# gps-carrier.net
KiCad netlist of a schematic drawn in EAGLE
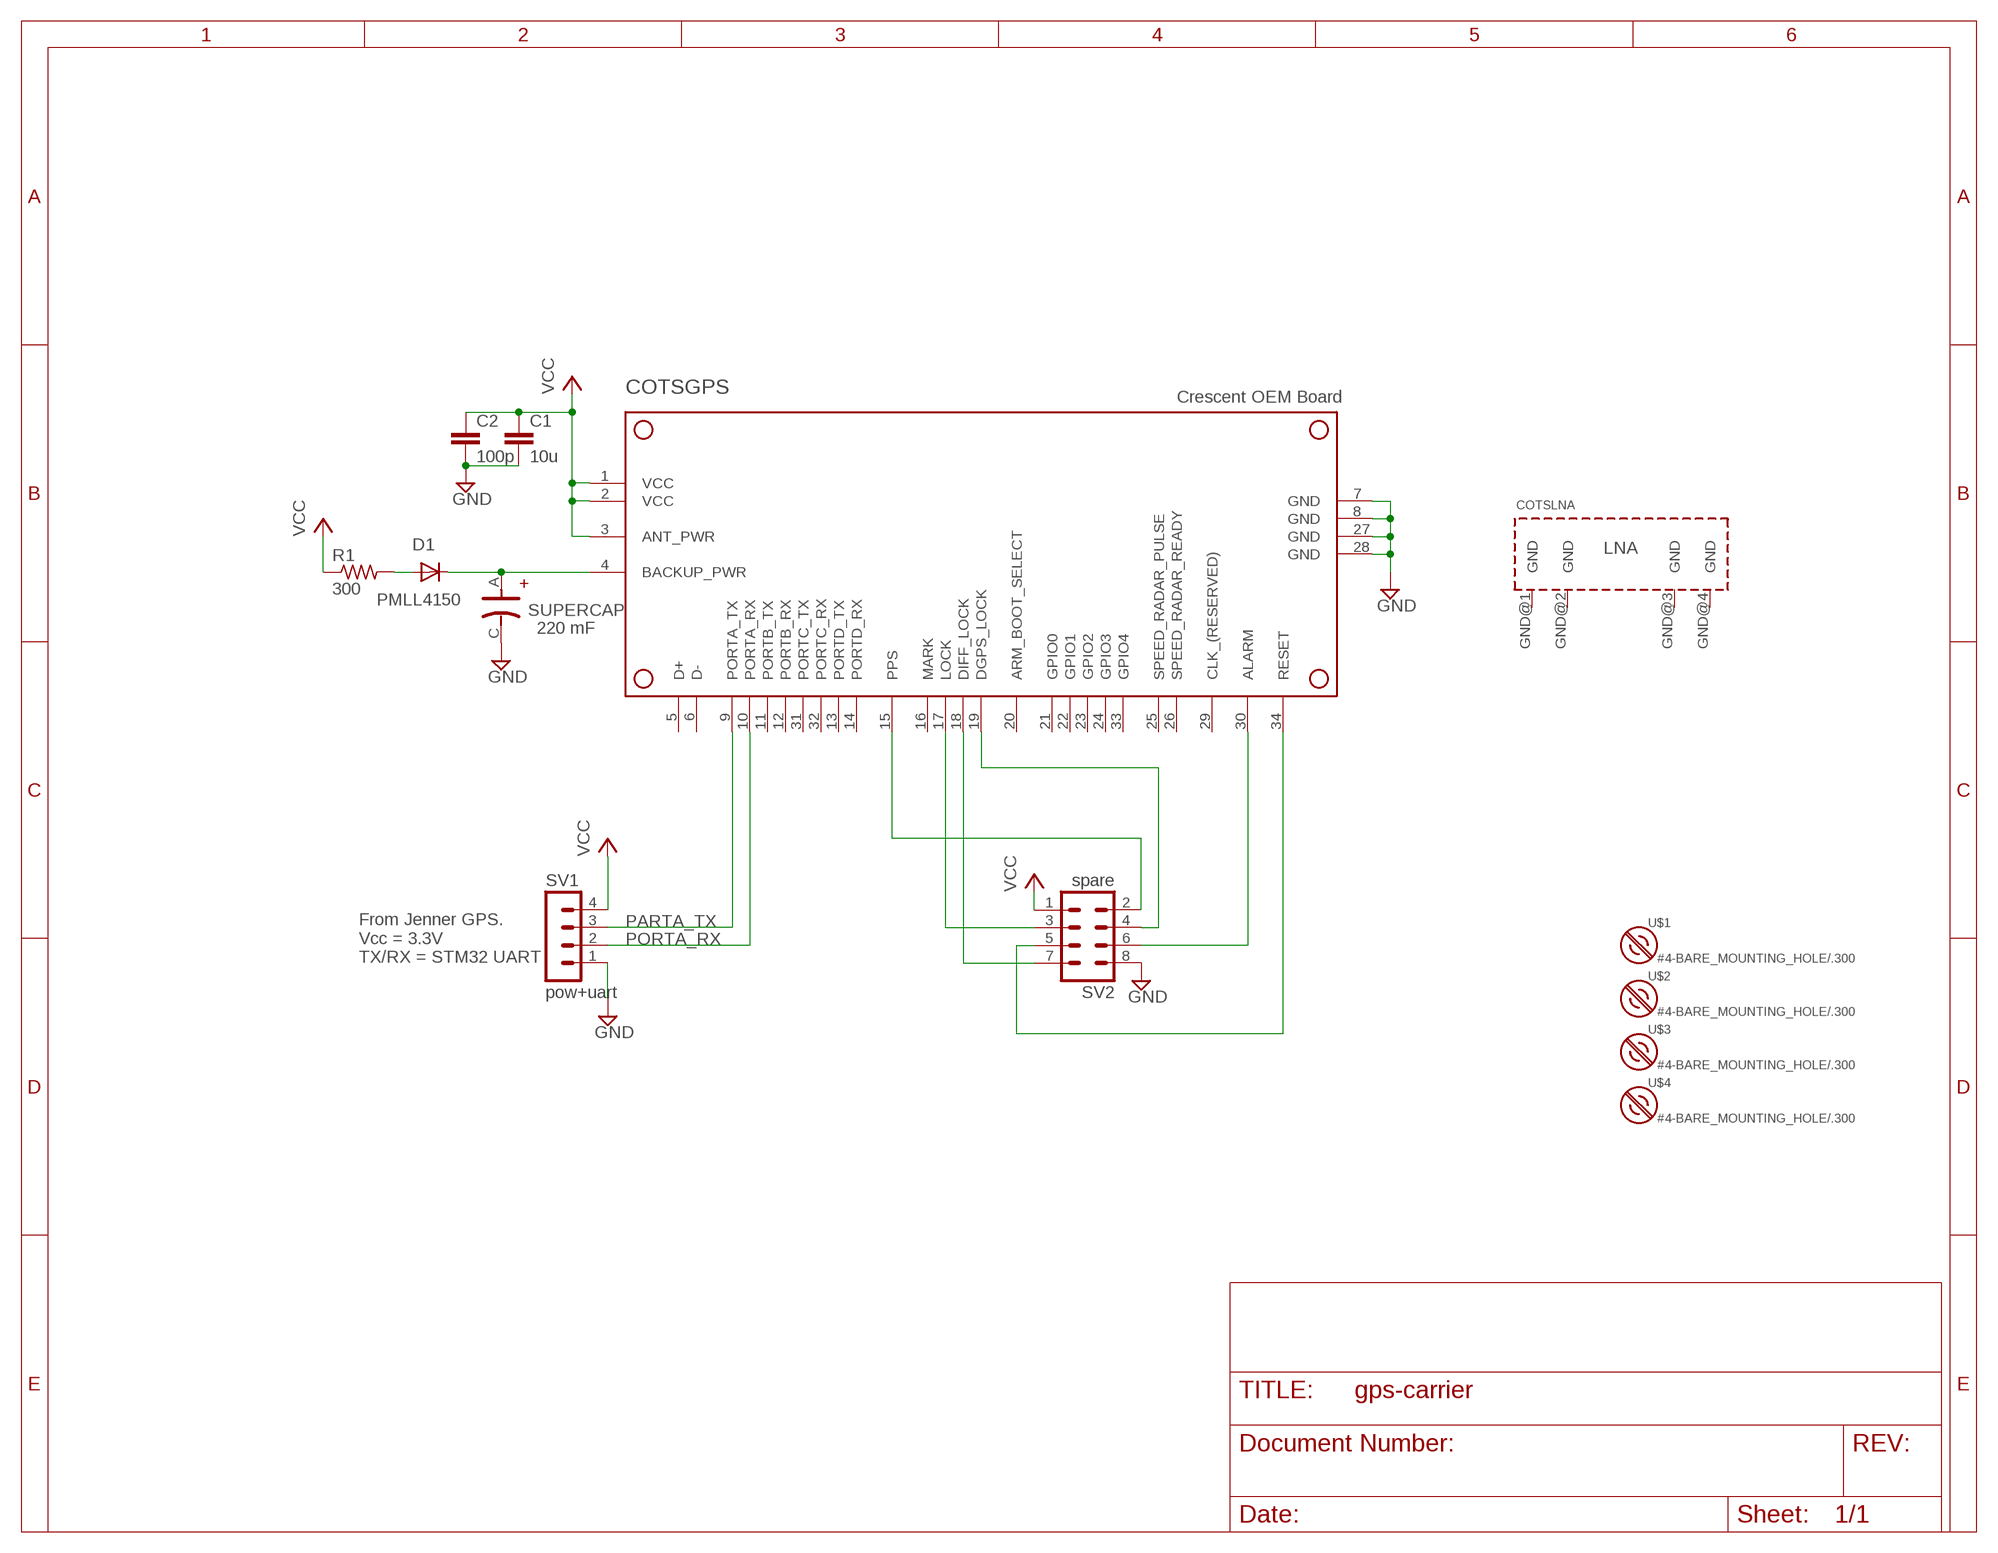
[diagram p0: schematic, sheet 1]

(export (version "E")
  (design (tool "Eeschema 10.0.6"))
  (components
    (comp (ref "C1")
      (value "10u")
      (footprint "eagle-import:C0805")
      (libsource (lib "eagle-import") (part "C-EUC0805"))
    )
    (comp (ref "C2")
      (value "100p")
      (footprint "eagle-import:C0603")
      (libsource (lib "eagle-import") (part "C-EUC0603"))
    )
    (comp (ref "COTSGPS")
      (value "HEMISPHERE_GPS_MOUNT")
      (footprint "eagle-import:GPS_CRECENT_OUTLINE")
      (libsource (lib "eagle-import") (part "HEMISPHERE_GPS_MOUNT"))
    )
    (comp (ref "COTSLNA")
      (value "GPS_LNA")
      (footprint "eagle-import:GPS_LNA")
      (libsource (lib "eagle-import") (part "GPS_LNA"))
    )
    (comp (ref "D1")
      (value "PMLL4150")
      (footprint "eagle-import:SOD80C")
      (libsource (lib "eagle-import") (part "PMLL4150"))
    )
    (comp (ref "R1")
      (value "300")
      (footprint "eagle-import:R0603")
      (libsource (lib "eagle-import") (part "R-US_R0603"))
    )
    (comp (ref "SUPERCAP")
      (value "220 mF")
      (footprint "eagle-import:DSK-HL")
      (libsource (lib "eagle-import") (part "DSK-3R3H224U-HL"))
    )
    (comp (ref "SV1")
      (value "pow+uart")
      (footprint "eagle-import:MA04-1")
      (libsource (lib "eagle-import") (part "MA04-1"))
    )
    (comp (ref "SV2")
      (value "spare")
      (footprint "eagle-import:MA04-2")
      (libsource (lib "eagle-import") (part "MA04-2"))
    )
    (comp (ref "U$1")
      (value "#4-BARE_MOUNTING_HOLE/.300")
      (footprint "eagle-import:#4_.300-BARE+STD_NUT_OR_STAR_WASHER")
      (libsource (lib "eagle-import") (part "#4-BARE_MOUNTING_HOLE/.300"))
    )
    (comp (ref "U$2")
      (value "#4-BARE_MOUNTING_HOLE/.300")
      (footprint "eagle-import:#4_.300-BARE+STD_NUT_OR_STAR_WASHER")
      (libsource (lib "eagle-import") (part "#4-BARE_MOUNTING_HOLE/.300"))
    )
    (comp (ref "U$3")
      (value "#4-BARE_MOUNTING_HOLE/.300")
      (footprint "eagle-import:#4_.300-BARE+STD_NUT_OR_STAR_WASHER")
      (libsource (lib "eagle-import") (part "#4-BARE_MOUNTING_HOLE/.300"))
    )
    (comp (ref "U$4")
      (value "#4-BARE_MOUNTING_HOLE/.300")
      (footprint "eagle-import:#4_.300-BARE+STD_NUT_OR_STAR_WASHER")
      (libsource (lib "eagle-import") (part "#4-BARE_MOUNTING_HOLE/.300"))
    )
  )
  (nets
    (net (code "1") (name "/PARTA_TX") (class "Default")
      (node (ref "COTSGPS") (pin "9") (pinfunction "PORTA_TX_9") (pintype "bidirectional"))
      (node (ref "SV1") (pin "3") (pinfunction "3_3") (pintype "passive"))
    )
    (net (code "2") (name "/PORTA_RX") (class "Default")
      (node (ref "COTSGPS") (pin "10") (pinfunction "PORTA_RX_10") (pintype "bidirectional"))
      (node (ref "SV1") (pin "2") (pinfunction "2_2") (pintype "passive"))
    )
    (net (code "3") (name "GND") (class "Default")
      (node (ref "C1") (pin "2") (pinfunction "2_2") (pintype "passive"))
      (node (ref "C2") (pin "2") (pinfunction "2_2") (pintype "passive"))
      (node (ref "COTSGPS") (pin "27") (pinfunction "GND_27") (pintype "bidirectional"))
      (node (ref "COTSGPS") (pin "28") (pinfunction "GND_28") (pintype "bidirectional"))
      (node (ref "COTSGPS") (pin "7") (pinfunction "GND_7") (pintype "bidirectional"))
      (node (ref "COTSGPS") (pin "8") (pinfunction "GND_8") (pintype "bidirectional"))
      (node (ref "SUPERCAP") (pin "C") (pinfunction "C_C") (pintype "bidirectional"))
      (node (ref "SV1") (pin "1") (pinfunction "1_1") (pintype "passive"))
      (node (ref "SV2") (pin "8") (pinfunction "8_8") (pintype "passive"))
    )
    (net (code "4") (name "Net-(COTSGPS-ALARM)") (class "Default")
      (node (ref "COTSGPS") (pin "30") (pinfunction "ALARM_30") (pintype "bidirectional"))
      (node (ref "SV2") (pin "6") (pinfunction "6_6") (pintype "passive"))
    )
    (net (code "5") (name "Net-(COTSGPS-BACKUP_PWR)") (class "Default")
      (node (ref "COTSGPS") (pin "4") (pinfunction "BACKUP_PWR_4") (pintype "bidirectional"))
      (node (ref "D1") (pin "C") (pinfunction "C_C") (pintype "passive"))
      (node (ref "SUPERCAP") (pin "A") (pinfunction "A_A") (pintype "bidirectional"))
    )
    (net (code "6") (name "Net-(COTSGPS-DGPS_LOCK)") (class "Default")
      (node (ref "COTSGPS") (pin "19") (pinfunction "DGPS_LOCK_19") (pintype "bidirectional"))
      (node (ref "SV2") (pin "4") (pinfunction "4_4") (pintype "passive"))
    )
    (net (code "7") (name "Net-(COTSGPS-DIFF_LOCK)") (class "Default")
      (node (ref "COTSGPS") (pin "18") (pinfunction "DIFF_LOCK_18") (pintype "bidirectional"))
      (node (ref "SV2") (pin "7") (pinfunction "7_7") (pintype "passive"))
    )
    (net (code "8") (name "Net-(COTSGPS-LOCK)") (class "Default")
      (node (ref "COTSGPS") (pin "17") (pinfunction "LOCK_17") (pintype "bidirectional"))
      (node (ref "SV2") (pin "3") (pinfunction "3_3") (pintype "passive"))
    )
    (net (code "9") (name "Net-(COTSGPS-PPS)") (class "Default")
      (node (ref "COTSGPS") (pin "15") (pinfunction "PPS_15") (pintype "bidirectional"))
      (node (ref "SV2") (pin "2") (pinfunction "2_2") (pintype "passive"))
    )
    (net (code "10") (name "Net-(COTSGPS-RESET)") (class "Default")
      (node (ref "COTSGPS") (pin "34") (pinfunction "RESET_34") (pintype "bidirectional"))
      (node (ref "SV2") (pin "5") (pinfunction "5_5") (pintype "passive"))
    )
    (net (code "11") (name "Net-(D1-PadA)") (class "Default")
      (node (ref "D1") (pin "A") (pinfunction "A_A") (pintype "passive"))
      (node (ref "R1") (pin "2") (pinfunction "2_2") (pintype "passive"))
    )
    (net (code "12") (name "VCC") (class "Default")
      (node (ref "C1") (pin "1") (pinfunction "1_1") (pintype "passive"))
      (node (ref "C2") (pin "1") (pinfunction "1_1") (pintype "passive"))
      (node (ref "COTSGPS") (pin "1") (pinfunction "VCC_1") (pintype "bidirectional"))
      (node (ref "COTSGPS") (pin "2") (pinfunction "VCC_2") (pintype "bidirectional"))
      (node (ref "COTSGPS") (pin "3") (pinfunction "ANT_PWR_3") (pintype "bidirectional"))
      (node (ref "R1") (pin "1") (pinfunction "1_1") (pintype "passive"))
      (node (ref "SV1") (pin "4") (pinfunction "4_4") (pintype "passive"))
      (node (ref "SV2") (pin "1") (pinfunction "1_1") (pintype "passive"))
    )
    (net (code "13") (name "unconnected-(COTSGPS-ARM_BOOT_SELECT-Pad20)") (class "Default")
      (node (ref "COTSGPS") (pin "20") (pinfunction "ARM_BOOT_SELECT_20") (pintype "bidirectional"))
    )
    (net (code "14") (name "unconnected-(COTSGPS-CLK_(RESERVED)-Pad29)") (class "Default")
      (node (ref "COTSGPS") (pin "29") (pinfunction "CLK_(RESERVED)_29") (pintype "bidirectional"))
    )
    (net (code "15") (name "unconnected-(COTSGPS-D+-Pad5)") (class "Default")
      (node (ref "COTSGPS") (pin "5") (pinfunction "D+_5") (pintype "bidirectional"))
    )
    (net (code "16") (name "unconnected-(COTSGPS-D--Pad6)") (class "Default")
      (node (ref "COTSGPS") (pin "6") (pinfunction "D-_6") (pintype "bidirectional"))
    )
    (net (code "17") (name "unconnected-(COTSGPS-GPIO0-Pad21)") (class "Default")
      (node (ref "COTSGPS") (pin "21") (pinfunction "GPIO0_21") (pintype "bidirectional"))
    )
    (net (code "18") (name "unconnected-(COTSGPS-GPIO1-Pad22)") (class "Default")
      (node (ref "COTSGPS") (pin "22") (pinfunction "GPIO1_22") (pintype "bidirectional"))
    )
    (net (code "19") (name "unconnected-(COTSGPS-GPIO2-Pad23)") (class "Default")
      (node (ref "COTSGPS") (pin "23") (pinfunction "GPIO2_23") (pintype "bidirectional"))
    )
    (net (code "20") (name "unconnected-(COTSGPS-GPIO3-Pad24)") (class "Default")
      (node (ref "COTSGPS") (pin "24") (pinfunction "GPIO3_24") (pintype "bidirectional"))
    )
    (net (code "21") (name "unconnected-(COTSGPS-GPIO4-Pad33)") (class "Default")
      (node (ref "COTSGPS") (pin "33") (pinfunction "GPIO4_33") (pintype "bidirectional"))
    )
    (net (code "22") (name "unconnected-(COTSGPS-MARK-Pad16)") (class "Default")
      (node (ref "COTSGPS") (pin "16") (pinfunction "MARK_16") (pintype "bidirectional"))
    )
    (net (code "23") (name "unconnected-(COTSGPS-PORTB_RX-Pad12)") (class "Default")
      (node (ref "COTSGPS") (pin "12") (pinfunction "PORTB_RX_12") (pintype "bidirectional"))
    )
    (net (code "24") (name "unconnected-(COTSGPS-PORTB_TX-Pad11)") (class "Default")
      (node (ref "COTSGPS") (pin "11") (pinfunction "PORTB_TX_11") (pintype "bidirectional"))
    )
    (net (code "25") (name "unconnected-(COTSGPS-PORTC_RX-Pad32)") (class "Default")
      (node (ref "COTSGPS") (pin "32") (pinfunction "PORTC_RX_32") (pintype "bidirectional"))
    )
    (net (code "26") (name "unconnected-(COTSGPS-PORTC_TX-Pad31)") (class "Default")
      (node (ref "COTSGPS") (pin "31") (pinfunction "PORTC_TX_31") (pintype "bidirectional"))
    )
    (net (code "27") (name "unconnected-(COTSGPS-PORTD_RX-Pad14)") (class "Default")
      (node (ref "COTSGPS") (pin "14") (pinfunction "PORTD_RX_14") (pintype "bidirectional"))
    )
    (net (code "28") (name "unconnected-(COTSGPS-PORTD_TX-Pad13)") (class "Default")
      (node (ref "COTSGPS") (pin "13") (pinfunction "PORTD_TX_13") (pintype "bidirectional"))
    )
    (net (code "29") (name "unconnected-(COTSGPS-SPEED_RADAR_PULSE-Pad25)") (class "Default")
      (node (ref "COTSGPS") (pin "25") (pinfunction "SPEED_RADAR_PULSE_25") (pintype "bidirectional"))
    )
    (net (code "30") (name "unconnected-(COTSGPS-SPEED_RADAR_READY-Pad26)") (class "Default")
      (node (ref "COTSGPS") (pin "26") (pinfunction "SPEED_RADAR_READY_26") (pintype "bidirectional"))
    )
    (net (code "31") (name "unconnected-(COTSLNA-GND-PadGND@1)") (class "Default")
      (node (ref "COTSLNA") (pin "GND@1") (pinfunction "GND_GND@1") (pintype "bidirectional"))
    )
    (net (code "32") (name "unconnected-(COTSLNA-GND-PadGND@2)") (class "Default")
      (node (ref "COTSLNA") (pin "GND@2") (pinfunction "GND_GND@2") (pintype "bidirectional"))
    )
    (net (code "33") (name "unconnected-(COTSLNA-GND-PadGND@3)") (class "Default")
      (node (ref "COTSLNA") (pin "GND@3") (pinfunction "GND_GND@3") (pintype "bidirectional"))
    )
    (net (code "34") (name "unconnected-(COTSLNA-GND-PadGND@4)") (class "Default")
      (node (ref "COTSLNA") (pin "GND@4") (pinfunction "GND_GND@4") (pintype "bidirectional"))
    )
  )
)
